# schematic.net
KiCad netlist of a schematic drawn in EAGLE
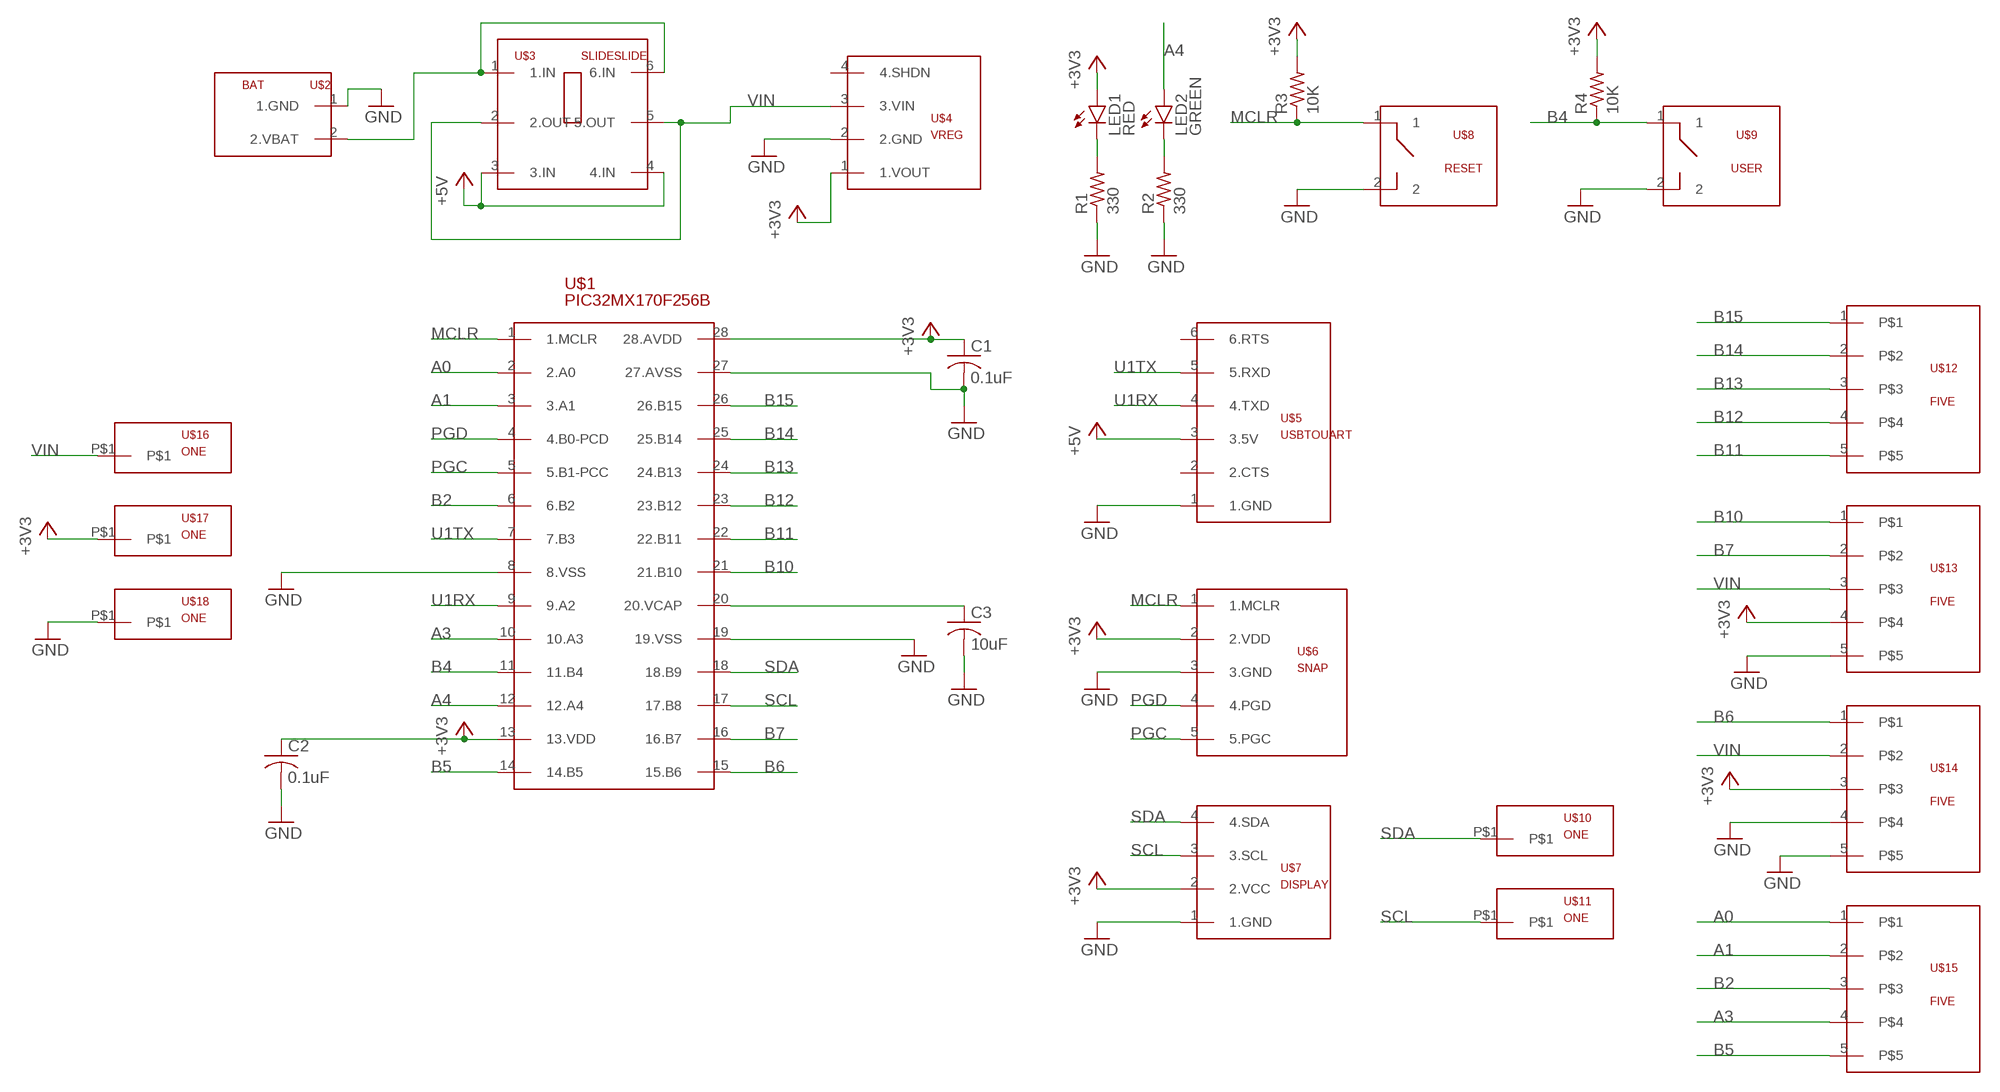
[diagram p0: schematic, sheet 1]

(export (version "E")
  (design (tool "Eeschema 10.0.6"))
  (components
    (comp (ref "C1")
      (value "0.1uF")
      (footprint "eagle-import:C025-024X044")
      (libsource (lib "eagle-import") (part "C-US025-024X044"))
    )
    (comp (ref "C2")
      (value "0.1uF")
      (footprint "eagle-import:C025-024X044")
      (libsource (lib "eagle-import") (part "C-US025-024X044"))
    )
    (comp (ref "C3")
      (value "10uF")
      (footprint "eagle-import:C025-024X044")
      (libsource (lib "eagle-import") (part "C-US025-024X044"))
    )
    (comp (ref "LED1")
      (value "RED")
      (footprint "eagle-import:LED3MM")
      (libsource (lib "eagle-import") (part "LED3MM"))
    )
    (comp (ref "LED2")
      (value "GREEN")
      (footprint "eagle-import:LED3MM")
      (libsource (lib "eagle-import") (part "LED3MM"))
    )
    (comp (ref "R1")
      (value "330")
      (footprint "eagle-import:0207_7")
      (libsource (lib "eagle-import") (part "R-US_0207/7"))
    )
    (comp (ref "R2")
      (value "330")
      (footprint "eagle-import:0207_7")
      (libsource (lib "eagle-import") (part "R-US_0207/7"))
    )
    (comp (ref "R3")
      (value "10K")
      (footprint "eagle-import:0207_7")
      (libsource (lib "eagle-import") (part "R-US_0207/7"))
    )
    (comp (ref "R4")
      (value "10K")
      (footprint "eagle-import:0207_7")
      (libsource (lib "eagle-import") (part "R-US_0207/7"))
    )
    (comp (ref "U$1")
      (value "PIC32MX170F256B")
      (footprint "eagle-import:DIL28-3")
      (libsource (lib "eagle-import") (part "PIC32MX170F256B"))
    )
    (comp (ref "U$2")
      (value "BAT")
      (footprint "eagle-import:BAT")
      (libsource (lib "eagle-import") (part "BAT"))
    )
    (comp (ref "U$3")
      (value "SLIDESLIDE")
      (footprint "eagle-import:SLIDE")
      (libsource (lib "eagle-import") (part "SLIDESLIDE"))
    )
    (comp (ref "U$4")
      (value "VREG")
      (footprint "eagle-import:VREG")
      (libsource (lib "eagle-import") (part "VREG"))
    )
    (comp (ref "U$5")
      (value "USBTOUART")
      (footprint "eagle-import:USBTOUART")
      (libsource (lib "eagle-import") (part "USBTOUART"))
    )
    (comp (ref "U$6")
      (value "SNAP")
      (footprint "eagle-import:SNAP")
      (libsource (lib "eagle-import") (part "SNAP"))
    )
    (comp (ref "U$7")
      (value "DISPLAY")
      (footprint "eagle-import:DISPLAY")
      (libsource (lib "eagle-import") (part "DISPLAY"))
    )
    (comp (ref "U$8")
      (value "RESET")
      (footprint "eagle-import:BUTTON")
      (libsource (lib "eagle-import") (part "BUTTON"))
    )
    (comp (ref "U$9")
      (value "USER")
      (footprint "eagle-import:BUTTON")
      (libsource (lib "eagle-import") (part "BUTTON"))
    )
    (comp (ref "U$10")
      (value "ONE")
      (footprint "eagle-import:ONE")
      (libsource (lib "eagle-import") (part "ONE"))
    )
    (comp (ref "U$11")
      (value "ONE")
      (footprint "eagle-import:ONE")
      (libsource (lib "eagle-import") (part "ONE"))
    )
    (comp (ref "U$12")
      (value "FIVE")
      (footprint "eagle-import:FIVE")
      (libsource (lib "eagle-import") (part "FIVE"))
    )
    (comp (ref "U$13")
      (value "FIVE")
      (footprint "eagle-import:FIVE")
      (libsource (lib "eagle-import") (part "FIVE"))
    )
    (comp (ref "U$14")
      (value "FIVE")
      (footprint "eagle-import:FIVE")
      (libsource (lib "eagle-import") (part "FIVE"))
    )
    (comp (ref "U$15")
      (value "FIVE")
      (footprint "eagle-import:FIVE")
      (libsource (lib "eagle-import") (part "FIVE"))
    )
    (comp (ref "U$16")
      (value "ONE")
      (footprint "eagle-import:ONE")
      (libsource (lib "eagle-import") (part "ONE"))
    )
    (comp (ref "U$17")
      (value "ONE")
      (footprint "eagle-import:ONE")
      (libsource (lib "eagle-import") (part "ONE"))
    )
    (comp (ref "U$18")
      (value "ONE")
      (footprint "eagle-import:ONE")
      (libsource (lib "eagle-import") (part "ONE"))
    )
  )
  (nets
    (net (code "1") (name "+3V3") (class "Default")
      (node (ref "C1") (pin "1") (pinfunction "1_1") (pintype "passive"))
      (node (ref "C2") (pin "1") (pinfunction "1_1") (pintype "passive"))
      (node (ref "LED1") (pin "A") (pinfunction "A_A") (pintype "passive"))
      (node (ref "R3") (pin "2") (pinfunction "2_2") (pintype "passive"))
      (node (ref "R4") (pin "2") (pinfunction "2_2") (pintype "passive"))
      (node (ref "U$1") (pin "13") (pinfunction "13.VDD_13") (pintype "bidirectional"))
      (node (ref "U$1") (pin "28") (pinfunction "28.AVDD_28") (pintype "bidirectional"))
      (node (ref "U$13") (pin "4") (pinfunction "P$4_4") (pintype "bidirectional"))
      (node (ref "U$14") (pin "3") (pinfunction "P$3_3") (pintype "bidirectional"))
      (node (ref "U$17") (pin "P$1") (pinfunction "P$1_P$1") (pintype "bidirectional"))
      (node (ref "U$4") (pin "1") (pinfunction "1.VOUT_1") (pintype "bidirectional"))
      (node (ref "U$6") (pin "2") (pinfunction "2.VDD_2") (pintype "bidirectional"))
      (node (ref "U$7") (pin "2") (pinfunction "2.VCC_2") (pintype "bidirectional"))
    )
    (net (code "2") (name "+5V") (class "Default")
      (node (ref "U$3") (pin "3") (pinfunction "3.IN_3") (pintype "bidirectional"))
      (node (ref "U$3") (pin "4") (pinfunction "4.IN_4") (pintype "bidirectional"))
      (node (ref "U$5") (pin "3") (pinfunction "3.5V_3") (pintype "bidirectional"))
    )
    (net (code "3") (name "/A0") (class "Default")
      (node (ref "U$1") (pin "2") (pinfunction "2.A0_2") (pintype "bidirectional"))
      (node (ref "U$15") (pin "1") (pinfunction "P$1_1") (pintype "bidirectional"))
    )
    (net (code "4") (name "/A1") (class "Default")
      (node (ref "U$1") (pin "3") (pinfunction "3.A1_3") (pintype "bidirectional"))
      (node (ref "U$15") (pin "2") (pinfunction "P$2_2") (pintype "bidirectional"))
    )
    (net (code "5") (name "/A3") (class "Default")
      (node (ref "U$1") (pin "10") (pinfunction "10.A3_10") (pintype "bidirectional"))
      (node (ref "U$15") (pin "4") (pinfunction "P$4_4") (pintype "bidirectional"))
    )
    (net (code "6") (name "/A4") (class "Default")
      (node (ref "LED2") (pin "A") (pinfunction "A_A") (pintype "passive"))
      (node (ref "U$1") (pin "12") (pinfunction "12.A4_12") (pintype "bidirectional"))
    )
    (net (code "7") (name "/B2") (class "Default")
      (node (ref "U$1") (pin "6") (pinfunction "6.B2_6") (pintype "bidirectional"))
      (node (ref "U$15") (pin "3") (pinfunction "P$3_3") (pintype "bidirectional"))
    )
    (net (code "8") (name "/B4") (class "Default")
      (node (ref "R4") (pin "1") (pinfunction "1_1") (pintype "passive"))
      (node (ref "U$1") (pin "11") (pinfunction "11.B4_11") (pintype "bidirectional"))
      (node (ref "U$9") (pin "1") (pinfunction "1_1") (pintype "bidirectional"))
    )
    (net (code "9") (name "/B5") (class "Default")
      (node (ref "U$1") (pin "14") (pinfunction "14.B5_14") (pintype "bidirectional"))
      (node (ref "U$15") (pin "5") (pinfunction "P$5_5") (pintype "bidirectional"))
    )
    (net (code "10") (name "/B6") (class "Default")
      (node (ref "U$1") (pin "15") (pinfunction "15.B6_15") (pintype "bidirectional"))
      (node (ref "U$14") (pin "1") (pinfunction "P$1_1") (pintype "bidirectional"))
    )
    (net (code "11") (name "/B7") (class "Default")
      (node (ref "U$1") (pin "16") (pinfunction "16.B7_16") (pintype "bidirectional"))
      (node (ref "U$13") (pin "2") (pinfunction "P$2_2") (pintype "bidirectional"))
    )
    (net (code "12") (name "/B10") (class "Default")
      (node (ref "U$1") (pin "21") (pinfunction "21.B10_21") (pintype "bidirectional"))
      (node (ref "U$13") (pin "1") (pinfunction "P$1_1") (pintype "bidirectional"))
    )
    (net (code "13") (name "/B11") (class "Default")
      (node (ref "U$1") (pin "22") (pinfunction "22.B11_22") (pintype "bidirectional"))
      (node (ref "U$12") (pin "5") (pinfunction "P$5_5") (pintype "bidirectional"))
    )
    (net (code "14") (name "/B12") (class "Default")
      (node (ref "U$1") (pin "23") (pinfunction "23.B12_23") (pintype "bidirectional"))
      (node (ref "U$12") (pin "4") (pinfunction "P$4_4") (pintype "bidirectional"))
    )
    (net (code "15") (name "/B13") (class "Default")
      (node (ref "U$1") (pin "24") (pinfunction "24.B13_24") (pintype "bidirectional"))
      (node (ref "U$12") (pin "3") (pinfunction "P$3_3") (pintype "bidirectional"))
    )
    (net (code "16") (name "/B14") (class "Default")
      (node (ref "U$1") (pin "25") (pinfunction "25.B14_25") (pintype "bidirectional"))
      (node (ref "U$12") (pin "2") (pinfunction "P$2_2") (pintype "bidirectional"))
    )
    (net (code "17") (name "/B15") (class "Default")
      (node (ref "U$1") (pin "26") (pinfunction "26.B15_26") (pintype "bidirectional"))
      (node (ref "U$12") (pin "1") (pinfunction "P$1_1") (pintype "bidirectional"))
    )
    (net (code "18") (name "/MCLR") (class "Default")
      (node (ref "R3") (pin "1") (pinfunction "1_1") (pintype "passive"))
      (node (ref "U$1") (pin "1") (pinfunction "1.MCLR_1") (pintype "bidirectional"))
      (node (ref "U$6") (pin "1") (pinfunction "1.MCLR_1") (pintype "bidirectional"))
      (node (ref "U$8") (pin "1") (pinfunction "1_1") (pintype "bidirectional"))
    )
    (net (code "19") (name "/PGC") (class "Default")
      (node (ref "U$1") (pin "5") (pinfunction "5.B1-PCC_5") (pintype "bidirectional"))
      (node (ref "U$6") (pin "5") (pinfunction "5.PGC_5") (pintype "bidirectional"))
    )
    (net (code "20") (name "/PGD") (class "Default")
      (node (ref "U$1") (pin "4") (pinfunction "4.B0-PCD_4") (pintype "bidirectional"))
      (node (ref "U$6") (pin "4") (pinfunction "4.PGD_4") (pintype "bidirectional"))
    )
    (net (code "21") (name "/SCL") (class "Default")
      (node (ref "U$1") (pin "17") (pinfunction "17.B8_17") (pintype "bidirectional"))
      (node (ref "U$11") (pin "P$1") (pinfunction "P$1_P$1") (pintype "bidirectional"))
      (node (ref "U$7") (pin "3") (pinfunction "3.SCL_3") (pintype "bidirectional"))
    )
    (net (code "22") (name "/SDA") (class "Default")
      (node (ref "U$1") (pin "18") (pinfunction "18.B9_18") (pintype "bidirectional"))
      (node (ref "U$10") (pin "P$1") (pinfunction "P$1_P$1") (pintype "bidirectional"))
      (node (ref "U$7") (pin "4") (pinfunction "4.SDA_4") (pintype "bidirectional"))
    )
    (net (code "23") (name "/U1RX") (class "Default")
      (node (ref "U$1") (pin "9") (pinfunction "9.A2_9") (pintype "bidirectional"))
      (node (ref "U$5") (pin "4") (pinfunction "4.TXD_4") (pintype "bidirectional"))
    )
    (net (code "24") (name "/U1TX") (class "Default")
      (node (ref "U$1") (pin "7") (pinfunction "7.B3_7") (pintype "bidirectional"))
      (node (ref "U$5") (pin "5") (pinfunction "5.RXD_5") (pintype "bidirectional"))
    )
    (net (code "25") (name "/VIN") (class "Default")
      (node (ref "U$13") (pin "3") (pinfunction "P$3_3") (pintype "bidirectional"))
      (node (ref "U$14") (pin "2") (pinfunction "P$2_2") (pintype "bidirectional"))
      (node (ref "U$16") (pin "P$1") (pinfunction "P$1_P$1") (pintype "bidirectional"))
      (node (ref "U$3") (pin "2") (pinfunction "2.OUT_2") (pintype "bidirectional"))
      (node (ref "U$3") (pin "5") (pinfunction "5.OUT_5") (pintype "bidirectional"))
      (node (ref "U$4") (pin "3") (pinfunction "3.VIN_3") (pintype "bidirectional"))
    )
    (net (code "26") (name "GND") (class "Default")
      (node (ref "C1") (pin "2") (pinfunction "2_2") (pintype "passive"))
      (node (ref "C2") (pin "2") (pinfunction "2_2") (pintype "passive"))
      (node (ref "C3") (pin "2") (pinfunction "2_2") (pintype "passive"))
      (node (ref "R1") (pin "1") (pinfunction "1_1") (pintype "passive"))
      (node (ref "R2") (pin "1") (pinfunction "1_1") (pintype "passive"))
      (node (ref "U$1") (pin "19") (pinfunction "19.VSS_19") (pintype "bidirectional"))
      (node (ref "U$1") (pin "27") (pinfunction "27.AVSS_27") (pintype "bidirectional"))
      (node (ref "U$1") (pin "8") (pinfunction "8.VSS_8") (pintype "bidirectional"))
      (node (ref "U$13") (pin "5") (pinfunction "P$5_5") (pintype "bidirectional"))
      (node (ref "U$14") (pin "4") (pinfunction "P$4_4") (pintype "bidirectional"))
      (node (ref "U$14") (pin "5") (pinfunction "P$5_5") (pintype "bidirectional"))
      (node (ref "U$18") (pin "P$1") (pinfunction "P$1_P$1") (pintype "bidirectional"))
      (node (ref "U$2") (pin "1") (pinfunction "1.GND_1") (pintype "bidirectional"))
      (node (ref "U$4") (pin "2") (pinfunction "2.GND_2") (pintype "bidirectional"))
      (node (ref "U$5") (pin "1") (pinfunction "1.GND_1") (pintype "bidirectional"))
      (node (ref "U$6") (pin "3") (pinfunction "3.GND_3") (pintype "bidirectional"))
      (node (ref "U$7") (pin "1") (pinfunction "1.GND_1") (pintype "bidirectional"))
      (node (ref "U$8") (pin "2") (pinfunction "2_2") (pintype "bidirectional"))
      (node (ref "U$9") (pin "2") (pinfunction "2_2") (pintype "bidirectional"))
    )
    (net (code "27") (name "Net-(LED1-C)") (class "Default")
      (node (ref "LED1") (pin "K") (pinfunction "C_K") (pintype "passive"))
      (node (ref "R1") (pin "2") (pinfunction "2_2") (pintype "passive"))
    )
    (net (code "28") (name "Net-(LED2-C)") (class "Default")
      (node (ref "LED2") (pin "K") (pinfunction "C_K") (pintype "passive"))
      (node (ref "R2") (pin "2") (pinfunction "2_2") (pintype "passive"))
    )
    (net (code "29") (name "Net-(U$1-20.VCAP)") (class "Default")
      (node (ref "C3") (pin "1") (pinfunction "1_1") (pintype "passive"))
      (node (ref "U$1") (pin "20") (pinfunction "20.VCAP_20") (pintype "bidirectional"))
    )
    (net (code "30") (name "Net-(U$2-2.VBAT)") (class "Default")
      (node (ref "U$2") (pin "2") (pinfunction "2.VBAT_2") (pintype "bidirectional"))
      (node (ref "U$3") (pin "1") (pinfunction "1.IN_1") (pintype "bidirectional"))
      (node (ref "U$3") (pin "6") (pinfunction "6.IN_6") (pintype "bidirectional"))
    )
    (net (code "31") (name "unconnected-(U$4-4.SHDN-Pad4)") (class "Default")
      (node (ref "U$4") (pin "4") (pinfunction "4.SHDN_4") (pintype "bidirectional"))
    )
    (net (code "32") (name "unconnected-(U$5-2.CTS-Pad2)") (class "Default")
      (node (ref "U$5") (pin "2") (pinfunction "2.CTS_2") (pintype "bidirectional"))
    )
    (net (code "33") (name "unconnected-(U$5-6.RTS-Pad6)") (class "Default")
      (node (ref "U$5") (pin "6") (pinfunction "6.RTS_6") (pintype "bidirectional"))
    )
  )
)
